# rc6551z80_18_v1.net
KiCad netlist of a schematic drawn in EAGLE
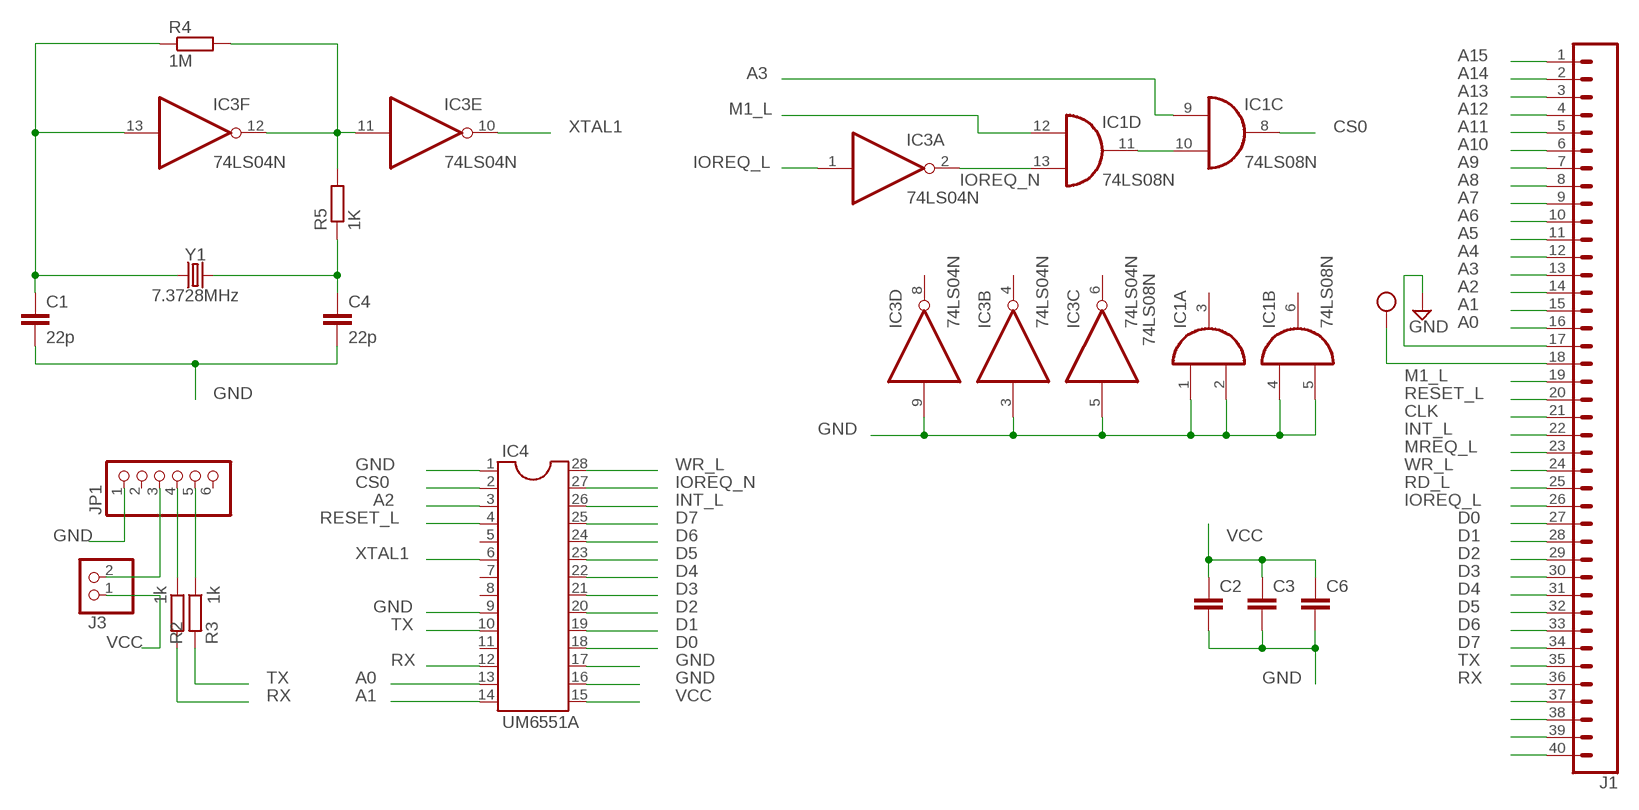
[diagram p0: schematic, sheet 1]

(export (version "E")
  (design (tool "Eeschema 10.0.6"))
  (components
    (comp (ref "C1")
      (value "22p")
      (footprint "eagle-import:C025-024X044")
      (libsource (lib "eagle-import") (part "rcl_334_C-EU025-024X044"))
    )
    (comp (ref "C2")
      (value "C-EU050-025X075")
      (footprint "eagle-import:C050-025X075")
      (libsource (lib "eagle-import") (part "C-EU050-025X075"))
    )
    (comp (ref "C3")
      (value "C-EU050-025X075")
      (footprint "eagle-import:C050-025X075")
      (libsource (lib "eagle-import") (part "C-EU050-025X075"))
    )
    (comp (ref "C4")
      (value "22p")
      (footprint "eagle-import:C025-024X044")
      (libsource (lib "eagle-import") (part "rcl_334_C-EU025-024X044"))
    )
    (comp (ref "C6")
      (value "C-EU050-025X075")
      (footprint "eagle-import:C050-025X075")
      (libsource (lib "eagle-import") (part "C-EU050-025X075"))
    )
    (comp (ref "IC1")
      (value "74LS08N")
      (footprint "eagle-import:DIL14")
      (libsource (lib "eagle-import") (part "7408NLS"))
    )
    (comp (ref "IC3")
      (value "74LS04N")
      (footprint "eagle-import:DIL14")
      (libsource (lib "eagle-import") (part "7404NLS"))
    )
    (comp (ref "IC4")
      (value "UM6551A")
      (footprint "eagle-import:DIL28-6")
      (libsource (lib "eagle-import") (part "DIL28"))
    )
    (comp (ref "J1")
      (value "CONN_40OFFSET")
      (footprint "eagle-import:1X40_OFFSET")
      (libsource (lib "eagle-import") (part "CONN_40OFFSET"))
    )
    (comp (ref "J3")
      (value "PINHD-1X2")
      (footprint "eagle-import:1X02")
      (libsource (lib "eagle-import") (part "PINHD-1X2"))
    )
    (comp (ref "JP1")
      (value "PINHD-1X6")
      (footprint "eagle-import:1X06")
      (libsource (lib "eagle-import") (part "PINHD-1X6"))
    )
    (comp (ref "R2")
      (value "1k")
      (footprint "eagle-import:0204_7")
      (libsource (lib "eagle-import") (part "R-EU_0204/7"))
    )
    (comp (ref "R3")
      (value "1k")
      (footprint "eagle-import:0204_7")
      (libsource (lib "eagle-import") (part "R-EU_0204/7"))
    )
    (comp (ref "R4")
      (value "1M")
      (footprint "eagle-import:0204_7")
      (libsource (lib "eagle-import") (part "R-EU_0204/7"))
    )
    (comp (ref "R5")
      (value "1K")
      (footprint "eagle-import:0204_7")
      (libsource (lib "eagle-import") (part "R-EU_0204/7"))
    )
    (comp (ref "Y1")
      (value "7.3728MHz")
      (footprint "eagle-import:HC49U")
      (libsource (lib "eagle-import") (part "CRYSTALPTH-HC49UV"))
    )
  )
  (nets
    (net (code "1") (name "/A0") (class "Default")
      (node (ref "IC4") (pin "13") (pinfunction "13_13") (pintype "passive"))
      (node (ref "J1") (pin "16") (pinfunction "16_16") (pintype "passive"))
    )
    (net (code "2") (name "/A1") (class "Default")
      (node (ref "IC4") (pin "14") (pinfunction "14_14") (pintype "passive"))
      (node (ref "J1") (pin "15") (pinfunction "15_15") (pintype "passive"))
    )
    (net (code "3") (name "/A2") (class "Default")
      (node (ref "IC4") (pin "3") (pinfunction "3_3") (pintype "passive"))
      (node (ref "J1") (pin "14") (pinfunction "14_14") (pintype "passive"))
    )
    (net (code "4") (name "/A3") (class "Default")
      (node (ref "IC1") (pin "9") (pinfunction "I0_9") (pintype "input"))
      (node (ref "J1") (pin "13") (pinfunction "13_13") (pintype "passive"))
    )
    (net (code "5") (name "/A4") (class "Default")
      (node (ref "J1") (pin "12") (pinfunction "12_12") (pintype "passive"))
    )
    (net (code "6") (name "/A5") (class "Default")
      (node (ref "J1") (pin "11") (pinfunction "11_11") (pintype "passive"))
    )
    (net (code "7") (name "/A6") (class "Default")
      (node (ref "J1") (pin "10") (pinfunction "10_10") (pintype "passive"))
    )
    (net (code "8") (name "/A7") (class "Default")
      (node (ref "J1") (pin "9") (pinfunction "9_9") (pintype "passive"))
    )
    (net (code "9") (name "/A8") (class "Default")
      (node (ref "J1") (pin "8") (pinfunction "8_8") (pintype "passive"))
    )
    (net (code "10") (name "/A9") (class "Default")
      (node (ref "J1") (pin "7") (pinfunction "7_7") (pintype "passive"))
    )
    (net (code "11") (name "/A10") (class "Default")
      (node (ref "J1") (pin "6") (pinfunction "6_6") (pintype "passive"))
    )
    (net (code "12") (name "/A11") (class "Default")
      (node (ref "J1") (pin "5") (pinfunction "5_5") (pintype "passive"))
    )
    (net (code "13") (name "/A12") (class "Default")
      (node (ref "J1") (pin "4") (pinfunction "4_4") (pintype "passive"))
    )
    (net (code "14") (name "/A13") (class "Default")
      (node (ref "J1") (pin "3") (pinfunction "3_3") (pintype "passive"))
    )
    (net (code "15") (name "/A14") (class "Default")
      (node (ref "J1") (pin "2") (pinfunction "2_2") (pintype "passive"))
    )
    (net (code "16") (name "/A15") (class "Default")
      (node (ref "J1") (pin "1") (pinfunction "1_1") (pintype "passive"))
    )
    (net (code "17") (name "/CLK") (class "Default")
      (node (ref "J1") (pin "21") (pinfunction "21_21") (pintype "passive"))
    )
    (net (code "18") (name "/CS0") (class "Default")
      (node (ref "IC1") (pin "8") (pinfunction "O_8") (pintype "output"))
      (node (ref "IC4") (pin "2") (pinfunction "2_2") (pintype "passive"))
    )
    (net (code "19") (name "/D0") (class "Default")
      (node (ref "IC4") (pin "18") (pinfunction "18_18") (pintype "passive"))
      (node (ref "J1") (pin "27") (pinfunction "27_27") (pintype "passive"))
    )
    (net (code "20") (name "/D1") (class "Default")
      (node (ref "IC4") (pin "19") (pinfunction "19_19") (pintype "passive"))
      (node (ref "J1") (pin "28") (pinfunction "28_28") (pintype "passive"))
    )
    (net (code "21") (name "/D2") (class "Default")
      (node (ref "IC4") (pin "20") (pinfunction "20_20") (pintype "passive"))
      (node (ref "J1") (pin "29") (pinfunction "29_29") (pintype "passive"))
    )
    (net (code "22") (name "/D3") (class "Default")
      (node (ref "IC4") (pin "21") (pinfunction "21_21") (pintype "passive"))
      (node (ref "J1") (pin "30") (pinfunction "30_30") (pintype "passive"))
    )
    (net (code "23") (name "/D4") (class "Default")
      (node (ref "IC4") (pin "22") (pinfunction "22_22") (pintype "passive"))
      (node (ref "J1") (pin "31") (pinfunction "31_31") (pintype "passive"))
    )
    (net (code "24") (name "/D5") (class "Default")
      (node (ref "IC4") (pin "23") (pinfunction "23_23") (pintype "passive"))
      (node (ref "J1") (pin "32") (pinfunction "32_32") (pintype "passive"))
    )
    (net (code "25") (name "/D6") (class "Default")
      (node (ref "IC4") (pin "24") (pinfunction "24_24") (pintype "passive"))
      (node (ref "J1") (pin "33") (pinfunction "33_33") (pintype "passive"))
    )
    (net (code "26") (name "/D7") (class "Default")
      (node (ref "IC4") (pin "25") (pinfunction "25_25") (pintype "passive"))
      (node (ref "J1") (pin "34") (pinfunction "34_34") (pintype "passive"))
    )
    (net (code "27") (name "/INT_L") (class "Default")
      (node (ref "IC4") (pin "26") (pinfunction "26_26") (pintype "passive"))
      (node (ref "J1") (pin "22") (pinfunction "22_22") (pintype "passive"))
    )
    (net (code "28") (name "/IOREQ_L") (class "Default")
      (node (ref "IC3") (pin "1") (pinfunction "I_1") (pintype "input"))
      (node (ref "J1") (pin "26") (pinfunction "26_26") (pintype "passive"))
    )
    (net (code "29") (name "/IOREQ_N") (class "Default")
      (node (ref "IC1") (pin "13") (pinfunction "I1_13") (pintype "input"))
      (node (ref "IC3") (pin "2") (pinfunction "O_2") (pintype "output"))
      (node (ref "IC4") (pin "27") (pinfunction "27_27") (pintype "passive"))
    )
    (net (code "30") (name "/M1_L") (class "Default")
      (node (ref "IC1") (pin "12") (pinfunction "I0_12") (pintype "input"))
      (node (ref "J1") (pin "19") (pinfunction "19_19") (pintype "passive"))
    )
    (net (code "31") (name "/MREQ_L") (class "Default")
      (node (ref "J1") (pin "23") (pinfunction "23_23") (pintype "passive"))
    )
    (net (code "32") (name "/RD_L") (class "Default")
      (node (ref "J1") (pin "25") (pinfunction "25_25") (pintype "passive"))
    )
    (net (code "33") (name "/RESET_L") (class "Default")
      (node (ref "IC4") (pin "4") (pinfunction "4_4") (pintype "passive"))
      (node (ref "J1") (pin "20") (pinfunction "20_20") (pintype "passive"))
    )
    (net (code "34") (name "/RX") (class "Default")
      (node (ref "IC4") (pin "12") (pinfunction "12_12") (pintype "passive"))
      (node (ref "J1") (pin "36") (pinfunction "36_36") (pintype "passive"))
      (node (ref "R2") (pin "2") (pinfunction "2_2") (pintype "passive"))
    )
    (net (code "35") (name "/TX") (class "Default")
      (node (ref "IC4") (pin "10") (pinfunction "10_10") (pintype "passive"))
      (node (ref "J1") (pin "35") (pinfunction "35_35") (pintype "passive"))
      (node (ref "R3") (pin "2") (pinfunction "2_2") (pintype "passive"))
    )
    (net (code "36") (name "/WR_L") (class "Default")
      (node (ref "IC4") (pin "28") (pinfunction "28_28") (pintype "passive"))
      (node (ref "J1") (pin "24") (pinfunction "24_24") (pintype "passive"))
    )
    (net (code "37") (name "/XTAL1") (class "Default")
      (node (ref "IC3") (pin "10") (pinfunction "O_10") (pintype "output"))
      (node (ref "IC4") (pin "6") (pinfunction "6_6") (pintype "passive"))
    )
    (net (code "38") (name "GND") (class "Default")
      (node (ref "C1") (pin "2") (pinfunction "2_2") (pintype "passive"))
      (node (ref "C2") (pin "2") (pinfunction "2_2") (pintype "passive"))
      (node (ref "C3") (pin "2") (pinfunction "2_2") (pintype "passive"))
      (node (ref "C4") (pin "2") (pinfunction "2_2") (pintype "passive"))
      (node (ref "C6") (pin "2") (pinfunction "2_2") (pintype "passive"))
      (node (ref "IC1") (pin "1") (pinfunction "I0_1") (pintype "input"))
      (node (ref "IC1") (pin "2") (pinfunction "I1_2") (pintype "input"))
      (node (ref "IC1") (pin "4") (pinfunction "I0_4") (pintype "input"))
      (node (ref "IC1") (pin "5") (pinfunction "I1_5") (pintype "input"))
      (node (ref "IC3") (pin "3") (pinfunction "I_3") (pintype "input"))
      (node (ref "IC3") (pin "5") (pinfunction "I_5") (pintype "input"))
      (node (ref "IC3") (pin "9") (pinfunction "I_9") (pintype "input"))
      (node (ref "IC4") (pin "1") (pinfunction "1_1") (pintype "passive"))
      (node (ref "IC4") (pin "16") (pinfunction "16_16") (pintype "passive"))
      (node (ref "IC4") (pin "17") (pinfunction "17_17") (pintype "passive"))
      (node (ref "IC4") (pin "9") (pinfunction "9_9") (pintype "passive"))
      (node (ref "J1") (pin "17") (pinfunction "17_17") (pintype "passive"))
      (node (ref "JP1") (pin "1") (pinfunction "1_1") (pintype "passive"))
    )
    (net (code "39") (name "Net-(C4-Pad1)") (class "Default")
      (node (ref "C4") (pin "1") (pinfunction "1_1") (pintype "passive"))
      (node (ref "R5") (pin "1") (pinfunction "1_1") (pintype "passive"))
      (node (ref "Y1") (pin "2") (pinfunction "2_2") (pintype "passive"))
    )
    (net (code "40") (name "Net-(IC1C-I1)") (class "Default")
      (node (ref "IC1") (pin "10") (pinfunction "I1_10") (pintype "input"))
      (node (ref "IC1") (pin "11") (pinfunction "O_11") (pintype "output"))
    )
    (net (code "41") (name "Net-(IC3E-I)") (class "Default")
      (node (ref "IC3") (pin "11") (pinfunction "I_11") (pintype "input"))
      (node (ref "IC3") (pin "12") (pinfunction "O_12") (pintype "output"))
      (node (ref "R4") (pin "2") (pinfunction "2_2") (pintype "passive"))
      (node (ref "R5") (pin "2") (pinfunction "2_2") (pintype "passive"))
    )
    (net (code "42") (name "Net-(IC3F-I)") (class "Default")
      (node (ref "C1") (pin "1") (pinfunction "1_1") (pintype "passive"))
      (node (ref "IC3") (pin "13") (pinfunction "I_13") (pintype "input"))
      (node (ref "R4") (pin "1") (pinfunction "1_1") (pintype "passive"))
      (node (ref "Y1") (pin "1") (pinfunction "1_1") (pintype "passive"))
    )
    (net (code "43") (name "Net-(J3-Pad2)") (class "Default")
      (node (ref "J3") (pin "2") (pinfunction "2_2") (pintype "passive"))
      (node (ref "JP1") (pin "3") (pinfunction "3_3") (pintype "passive"))
    )
    (net (code "44") (name "Net-(JP1-Pad4)") (class "Default")
      (node (ref "JP1") (pin "4") (pinfunction "4_4") (pintype "passive"))
      (node (ref "R2") (pin "1") (pinfunction "1_1") (pintype "passive"))
    )
    (net (code "45") (name "Net-(JP1-Pad5)") (class "Default")
      (node (ref "JP1") (pin "5") (pinfunction "5_5") (pintype "passive"))
      (node (ref "R3") (pin "1") (pinfunction "1_1") (pintype "passive"))
    )
    (net (code "46") (name "VCC") (class "Default")
      (node (ref "C2") (pin "1") (pinfunction "1_1") (pintype "passive"))
      (node (ref "C3") (pin "1") (pinfunction "1_1") (pintype "passive"))
      (node (ref "C6") (pin "1") (pinfunction "1_1") (pintype "passive"))
      (node (ref "IC4") (pin "15") (pinfunction "15_15") (pintype "passive"))
      (node (ref "J1") (pin "18") (pinfunction "18_18") (pintype "passive"))
      (node (ref "J3") (pin "1") (pinfunction "1_1") (pintype "passive"))
    )
    (net (code "47") (name "unconnected-(IC1A-O-Pad3)") (class "Default")
      (node (ref "IC1") (pin "3") (pinfunction "O_3") (pintype "output"))
    )
    (net (code "48") (name "unconnected-(IC1B-O-Pad6)") (class "Default")
      (node (ref "IC1") (pin "6") (pinfunction "O_6") (pintype "output"))
    )
    (net (code "49") (name "unconnected-(IC3B-O-Pad4)") (class "Default")
      (node (ref "IC3") (pin "4") (pinfunction "O_4") (pintype "output"))
    )
    (net (code "50") (name "unconnected-(IC3C-O-Pad6)") (class "Default")
      (node (ref "IC3") (pin "6") (pinfunction "O_6") (pintype "output"))
    )
    (net (code "51") (name "unconnected-(IC3D-O-Pad8)") (class "Default")
      (node (ref "IC3") (pin "8") (pinfunction "O_8") (pintype "output"))
    )
    (net (code "52") (name "unconnected-(IC4-Pad5)") (class "Default")
      (node (ref "IC4") (pin "5") (pinfunction "5_5") (pintype "passive"))
    )
    (net (code "53") (name "unconnected-(IC4-Pad7)") (class "Default")
      (node (ref "IC4") (pin "7") (pinfunction "7_7") (pintype "passive"))
    )
    (net (code "54") (name "unconnected-(IC4-Pad8)") (class "Default")
      (node (ref "IC4") (pin "8") (pinfunction "8_8") (pintype "passive"))
    )
    (net (code "55") (name "unconnected-(IC4-Pad11)") (class "Default")
      (node (ref "IC4") (pin "11") (pinfunction "11_11") (pintype "passive"))
    )
    (net (code "56") (name "unconnected-(J1-Pad37)") (class "Default")
      (node (ref "J1") (pin "37") (pinfunction "37_37") (pintype "passive"))
    )
    (net (code "57") (name "unconnected-(J1-Pad38)") (class "Default")
      (node (ref "J1") (pin "38") (pinfunction "38_38") (pintype "passive"))
    )
    (net (code "58") (name "unconnected-(J1-Pad39)") (class "Default")
      (node (ref "J1") (pin "39") (pinfunction "39_39") (pintype "passive"))
    )
    (net (code "59") (name "unconnected-(J1-Pad40)") (class "Default")
      (node (ref "J1") (pin "40") (pinfunction "40_40") (pintype "passive"))
    )
    (net (code "60") (name "unconnected-(JP1-Pad2)") (class "Default")
      (node (ref "JP1") (pin "2") (pinfunction "2_2") (pintype "passive"))
    )
    (net (code "61") (name "unconnected-(JP1-Pad6)") (class "Default")
      (node (ref "JP1") (pin "6") (pinfunction "6_6") (pintype "passive"))
    )
  )
)
